# MT3608.net
KiCad netlist of a schematic drawn in Altium Designer
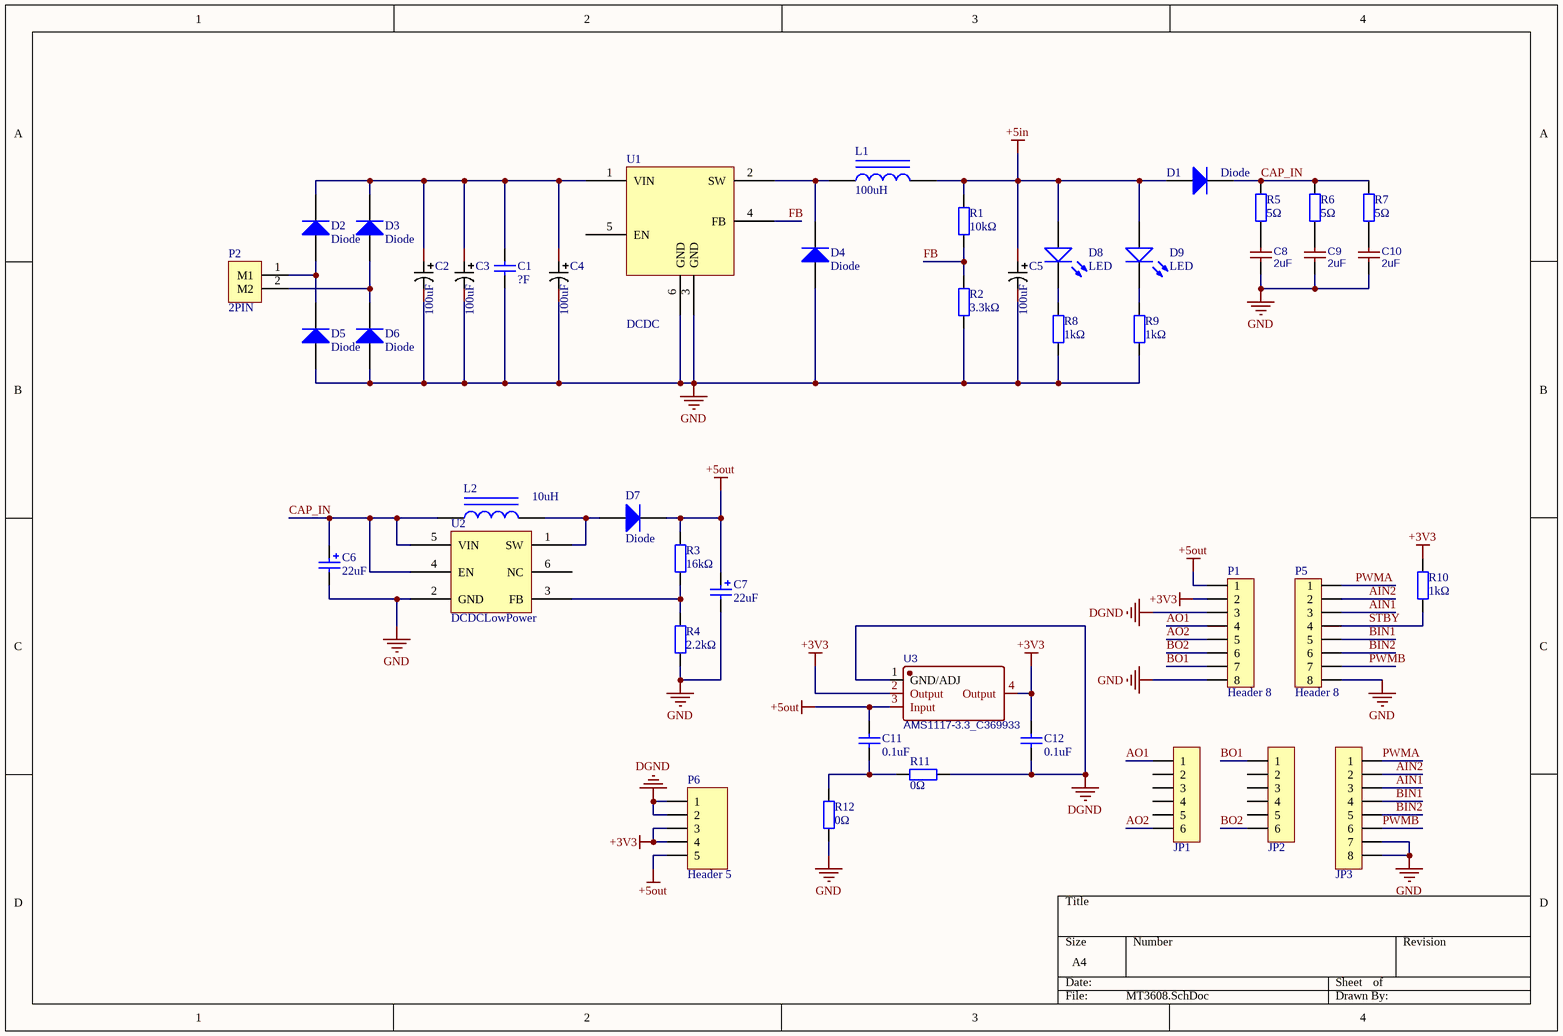
[diagram p0: MT3608.SchDoc]

(export (version "E")
  (design (tool "Eeschema 10.0.6"))
  (components
    (comp (ref "C1")
      (value "?F")
      (footprint "0603_C")
      (description "贴片电容")
      (libsource (lib "SFerret") (part "SMT_Cap"))
    )
    (comp (ref "C2")
      (value "100uF")
      (footprint "CM E(8*10.2)")
      (description "贴片电容")
      (libsource (lib "SFerret") (part "SMT_Cap_Electrolytic"))
    )
    (comp (ref "C3")
      (value "100uF")
      (footprint "CM E(8*10.2)")
      (description "贴片电容")
      (libsource (lib "SFerret") (part "SMT_Cap_Electrolytic"))
    )
    (comp (ref "C4")
      (value "100uF")
      (footprint "CM E(8*10.2)")
      (description "贴片电容")
      (libsource (lib "SFerret") (part "SMT_Cap_Electrolytic"))
    )
    (comp (ref "C5")
      (value "100uF")
      (footprint "CM E(8*10.2)")
      (description "贴片电容")
      (libsource (lib "SFerret") (part "SMT_Cap_Electrolytic"))
    )
    (comp (ref "C6")
      (value "22uF")
      (footprint "CASE-C_6032")
      (description "钽电容")
      (libsource (lib "SFerret") (part "SMT_Cap_Tantalum"))
    )
    (comp (ref "C7")
      (value "22uF")
      (footprint "CASE-C_6032")
      (description "钽电容")
      (libsource (lib "SFerret") (part "SMT_Cap_Tantalum"))
    )
    (comp (ref "C8")
      (value "2uF")
      (footprint "CAP-TH_L23.0-W10.0-P20.00-D1.4")
      (description "CBB，2uF电容")
      (fields
        (field (name "BOM_MANUFACTURER PART") "MPP205J4241119LC")
        (field (name "BOM_SUPPLIER PART") "C93266")
      )
      (libsource (lib "Schlib1") (part "2uF-CBB"))
    )
    (comp (ref "C9")
      (value "2uF")
      (footprint "CAP-TH_L23.0-W10.0-P20.00-D1.4")
      (description "CBB，2uF电容")
      (fields
        (field (name "BOM_MANUFACTURER PART") "MPP205J4241119LC")
        (field (name "BOM_SUPPLIER PART") "C93266")
      )
      (libsource (lib "Schlib1") (part "2uF-CBB"))
    )
    (comp (ref "C10")
      (value "2uF")
      (footprint "CAP-TH_L23.0-W10.0-P20.00-D1.4")
      (description "CBB，2uF电容")
      (fields
        (field (name "BOM_MANUFACTURER PART") "MPP205J4241119LC")
        (field (name "BOM_SUPPLIER PART") "C93266")
      )
      (libsource (lib "Schlib1") (part "2uF-CBB"))
    )
    (comp (ref "C11")
      (value "0.1uF")
      (footprint "0603_C")
      (description "贴片电容")
      (libsource (lib "SFerret") (part "SMT_Cap"))
    )
    (comp (ref "C12")
      (value "0.1uF")
      (footprint "0603_C")
      (description "贴片电容")
      (libsource (lib "SFerret") (part "SMT_Cap"))
    )
    (comp (ref "D1")
      (value "Diode")
      (footprint "SMA(DO-214AC)_S1")
      (description "通用二极管")
      (libsource (lib "SFerret") (part "Diode"))
    )
    (comp (ref "D2")
      (value "Diode")
      (footprint "SMA(DO-214AC)_S2")
      (description "通用二极管")
      (libsource (lib "SFerret") (part "Diode"))
    )
    (comp (ref "D3")
      (value "Diode")
      (footprint "SMA(DO-214AC)_S2")
      (description "通用二极管")
      (libsource (lib "SFerret") (part "Diode"))
    )
    (comp (ref "D4")
      (value "Diode")
      (footprint "SMA(DO-214AC)_S1")
      (description "通用二极管")
      (libsource (lib "SFerret") (part "Diode"))
    )
    (comp (ref "D5")
      (value "Diode")
      (footprint "SMA(DO-214AC)_S2")
      (description "通用二极管")
      (libsource (lib "SFerret") (part "Diode"))
    )
    (comp (ref "D6")
      (value "Diode")
      (footprint "SMA(DO-214AC)_S2")
      (description "通用二极管")
      (libsource (lib "SFerret") (part "Diode"))
    )
    (comp (ref "D7")
      (value "Diode")
      (footprint "SMA(DO-214AC)_S1")
      (description "通用二极管")
      (libsource (lib "SFerret") (part "Diode"))
    )
    (comp (ref "D8")
      (value "LED")
      (footprint "0805_LED")
      (description "发光二极管")
      (libsource (lib "SFerret") (part "LED"))
    )
    (comp (ref "D9")
      (value "LED")
      (footprint "0805_LED")
      (description "发光二极管")
      (libsource (lib "SFerret") (part "LED"))
    )
    (comp (ref "JP1")
      (value "HDR-1X6")
      (footprint "HDR2.54-WS-6P")
      (description "6P接插件")
      (libsource (lib "SFerret") (part "Header 6"))
    )
    (comp (ref "JP2")
      (value "HDR-1X6")
      (footprint "HDR2.54-WS-6P")
      (description "6P接插件")
      (libsource (lib "SFerret") (part "Header 6"))
    )
    (comp (ref "JP3")
      (value "HDR-1X8")
      (footprint "HDR2.54-WS-8P")
      (description "8P接插件")
      (libsource (lib "SFerret") (part "Header 8"))
    )
    (comp (ref "L1")
      (value "100uH")
      (footprint "CDRH127")
      (description "功率电感")
      (libsource (lib "SFerret") (part "SMT_Iud_Power"))
    )
    (comp (ref "L2")
      (value "10uH")
      (footprint "CDRH73")
      (description "功率电感")
      (libsource (lib "SFerret") (part "SMT_Iud_Power"))
    )
    (comp (ref "P1")
      (value "Header 8")
      (footprint "Header 8")
      (description "排针")
      (libsource (lib "") (part "Header 8_1"))
    )
    (comp (ref "P2") (value "2PIN") (footprint "KF128-2P") (libsource (lib "集大电协1.5") (part "接线端子-2PIN")))
    (comp (ref "P5")
      (value "Header 8")
      (footprint "Header 8")
      (description "排针")
      (libsource (lib "集大电协1.5") (part "Header 8"))
    )
    (comp (ref "P6")
      (value "Header 5")
      (footprint "HDR2.54-WS-5P")
      (description "排针")
      (libsource (lib "SFerret") (part "Header 5"))
    )
    (comp (ref "R1")
      (value "10kΩ")
      (footprint "0603_R")
      (description "贴片电阻")
      (libsource (lib "SFerret") (part "SMT_Res"))
    )
    (comp (ref "R2")
      (value "3.3kΩ")
      (footprint "0603_R")
      (description "贴片电阻")
      (libsource (lib "SFerret") (part "SMT_Res"))
    )
    (comp (ref "R3")
      (value "16kΩ")
      (footprint "0603_R")
      (description "贴片电阻")
      (libsource (lib "SFerret") (part "SMT_Res"))
    )
    (comp (ref "R4")
      (value "2.2kΩ")
      (footprint "0603_R")
      (description "贴片电阻")
      (libsource (lib "SFerret") (part "SMT_Res"))
    )
    (comp (ref "R5")
      (value "5Ω")
      (footprint "0603_R")
      (description "贴片电阻")
      (libsource (lib "SFerret") (part "SMT_Res"))
    )
    (comp (ref "R6")
      (value "5Ω")
      (footprint "0603_R")
      (description "贴片电阻")
      (libsource (lib "SFerret") (part "SMT_Res"))
    )
    (comp (ref "R7")
      (value "5Ω")
      (footprint "0603_R")
      (description "贴片电阻")
      (libsource (lib "SFerret") (part "SMT_Res"))
    )
    (comp (ref "R8")
      (value "1kΩ")
      (footprint "0603_R")
      (description "贴片电阻")
      (libsource (lib "SFerret") (part "SMT_Res"))
    )
    (comp (ref "R9")
      (value "1kΩ")
      (footprint "0603_R")
      (description "贴片电阻")
      (libsource (lib "SFerret") (part "SMT_Res"))
    )
    (comp (ref "R10")
      (value "1kΩ")
      (footprint "0603_R")
      (description "贴片电阻")
      (libsource (lib "SFerret") (part "SMT_Res"))
    )
    (comp (ref "R11")
      (value "0Ω")
      (footprint "1206_R")
      (description "贴片电阻")
      (libsource (lib "") (part "SMT_Res_1"))
    )
    (comp (ref "R12")
      (value "0Ω")
      (footprint "1206_R")
      (description "贴片电阻")
      (libsource (lib "SFerret") (part "SMT_Res"))
    )
    (comp (ref "U1")
      (value "DCDC")
      (footprint "TO-252-XL")
      (description "宽输入DCDC升降压管理芯片（Buck）")
      (libsource (lib "SFerret") (part "XL7015"))
    )
    (comp (ref "U2")
      (value "DCDCLowPower")
      (footprint "SOT95P290X145-6N")
      (libsource (lib "SFerret") (part "MT3608"))
    )
    (comp (ref "U3")
      (value "AMS1117-3.3_C369933")
      (footprint "SOT-223-4_L6.5-W3.5-P2.30-LS7.0-BR")
      (fields
        (field (name "BOM_SUPPLIER PART") "C369933")
        (field (name "BOM_MANUFACTURER PART") "AMS1117-3.3")
        (field (name "CONTRIBUTOR") "LCSC")
      )
      (libsource (lib "Schlib1") (part "AMS1117-3.3_C369933"))
    )
  )
  (nets
    (net (code "1") (name "+3V3") (class "Default")
      (node (ref "C12") (pin "2") (pinfunction "2_2") (pintype "passive"))
      (node (ref "P1") (pin "2") (pinfunction "2_2") (pintype "passive"))
      (node (ref "P6") (pin "3") (pinfunction "3_3") (pintype "passive"))
      (node (ref "P6") (pin "4") (pinfunction "4_4") (pintype "passive"))
      (node (ref "R10") (pin "2") (pinfunction "2_2") (pintype "passive"))
      (node (ref "U3") (pin "2") (pinfunction "Output_2") (pintype "passive"))
      (node (ref "U3") (pin "4") (pinfunction "Output_4") (pintype "passive"))
    )
    (net (code "2") (name "+5in") (class "Default")
      (node (ref "C5") (pin "1") (pinfunction "1_1") (pintype "passive"))
      (node (ref "D1") (pin "1") (pinfunction "A_1") (pintype "passive"))
      (node (ref "D8") (pin "A") (pinfunction "A_A") (pintype "passive"))
      (node (ref "D9") (pin "A") (pinfunction "A_A") (pintype "passive"))
      (node (ref "L1") (pin "2") (pinfunction "2_2") (pintype "passive"))
      (node (ref "R1") (pin "2") (pinfunction "2_2") (pintype "passive"))
    )
    (net (code "3") (name "+5out") (class "Default")
      (node (ref "C11") (pin "2") (pinfunction "2_2") (pintype "passive"))
      (node (ref "C7") (pin "1") (pinfunction "1_1") (pintype "passive"))
      (node (ref "D7") (pin "2") (pinfunction "K_2") (pintype "passive"))
      (node (ref "P1") (pin "1") (pinfunction "1_1") (pintype "passive"))
      (node (ref "P6") (pin "5") (pinfunction "5_5") (pintype "passive"))
      (node (ref "R3") (pin "2") (pinfunction "2_2") (pintype "passive"))
      (node (ref "U3") (pin "3") (pinfunction "Input_3") (pintype "passive"))
    )
    (net (code "4") (name "/AIN1") (class "Default")
      (node (ref "JP3") (pin "3") (pinfunction "3_3") (pintype "passive"))
      (node (ref "P5") (pin "3") (pinfunction "3_3") (pintype "passive"))
    )
    (net (code "5") (name "/AIN2") (class "Default")
      (node (ref "JP3") (pin "2") (pinfunction "2_2") (pintype "passive"))
      (node (ref "P5") (pin "2") (pinfunction "2_2") (pintype "passive"))
    )
    (net (code "6") (name "/AO1") (class "Default")
      (node (ref "JP1") (pin "1") (pinfunction "1_1") (pintype "passive"))
      (node (ref "P1") (pin "4") (pinfunction "4_4") (pintype "passive"))
    )
    (net (code "7") (name "/AO2") (class "Default")
      (node (ref "JP1") (pin "6") (pinfunction "6_6") (pintype "passive"))
      (node (ref "P1") (pin "5") (pinfunction "5_5") (pintype "passive"))
    )
    (net (code "8") (name "/BIN1") (class "Default")
      (node (ref "JP3") (pin "4") (pinfunction "4_4") (pintype "passive"))
      (node (ref "P5") (pin "5") (pinfunction "5_5") (pintype "passive"))
    )
    (net (code "9") (name "/BIN2") (class "Default")
      (node (ref "JP3") (pin "5") (pinfunction "5_5") (pintype "passive"))
      (node (ref "P5") (pin "6") (pinfunction "6_6") (pintype "passive"))
    )
    (net (code "10") (name "/BO1") (class "Default")
      (node (ref "JP2") (pin "1") (pinfunction "1_1") (pintype "passive"))
      (node (ref "P1") (pin "7") (pinfunction "7_7") (pintype "passive"))
    )
    (net (code "11") (name "/BO2") (class "Default")
      (node (ref "JP2") (pin "6") (pinfunction "6_6") (pintype "passive"))
      (node (ref "P1") (pin "6") (pinfunction "6_6") (pintype "passive"))
    )
    (net (code "12") (name "/CAP_IN") (class "Default")
      (node (ref "C6") (pin "1") (pinfunction "1_1") (pintype "passive"))
      (node (ref "D1") (pin "2") (pinfunction "K_2") (pintype "passive"))
      (node (ref "L2") (pin "1") (pinfunction "1_1") (pintype "passive"))
      (node (ref "R5") (pin "2") (pinfunction "2_2") (pintype "passive"))
      (node (ref "R6") (pin "2") (pinfunction "2_2") (pintype "passive"))
      (node (ref "R7") (pin "2") (pinfunction "2_2") (pintype "passive"))
      (node (ref "U2") (pin "4") (pinfunction "EN_4") (pintype "passive"))
      (node (ref "U2") (pin "5") (pinfunction "VIN_5") (pintype "passive"))
    )
    (net (code "13") (name "/FB") (class "Default")
      (node (ref "R1") (pin "1") (pinfunction "1_1") (pintype "passive"))
      (node (ref "R2") (pin "2") (pinfunction "2_2") (pintype "passive"))
      (node (ref "U1") (pin "4") (pinfunction "FB_4") (pintype "passive"))
    )
    (net (code "14") (name "/PWMA") (class "Default")
      (node (ref "JP3") (pin "1") (pinfunction "1_1") (pintype "passive"))
      (node (ref "P5") (pin "1") (pinfunction "1_1") (pintype "passive"))
    )
    (net (code "15") (name "/PWMB") (class "Default")
      (node (ref "JP3") (pin "6") (pinfunction "6_6") (pintype "passive"))
      (node (ref "P5") (pin "7") (pinfunction "7_7") (pintype "passive"))
    )
    (net (code "16") (name "/STBY") (class "Default")
      (node (ref "P5") (pin "4") (pinfunction "4_4") (pintype "passive"))
      (node (ref "R10") (pin "1") (pinfunction "1_1") (pintype "passive"))
    )
    (net (code "17") (name "DGND") (class "Default")
      (node (ref "C12") (pin "1") (pinfunction "1_1") (pintype "passive"))
      (node (ref "P1") (pin "3") (pinfunction "3_3") (pintype "passive"))
      (node (ref "P6") (pin "1") (pinfunction "1_1") (pintype "passive"))
      (node (ref "P6") (pin "2") (pinfunction "2_2") (pintype "passive"))
      (node (ref "R11") (pin "1") (pinfunction "1_1") (pintype "passive"))
      (node (ref "U3") (pin "1") (pinfunction "GND/ADJ_1") (pintype "passive"))
    )
    (net (code "18") (name "GND") (class "Default")
      (node (ref "C1") (pin "1") (pinfunction "1_1") (pintype "passive"))
      (node (ref "C10") (pin "1") (pinfunction "1_1") (pintype "passive"))
      (node (ref "C2") (pin "2") (pinfunction "2_2") (pintype "passive"))
      (node (ref "C3") (pin "2") (pinfunction "2_2") (pintype "passive"))
      (node (ref "C4") (pin "2") (pinfunction "2_2") (pintype "passive"))
      (node (ref "C5") (pin "2") (pinfunction "2_2") (pintype "passive"))
      (node (ref "C6") (pin "2") (pinfunction "2_2") (pintype "passive"))
      (node (ref "C7") (pin "2") (pinfunction "2_2") (pintype "passive"))
      (node (ref "C8") (pin "1") (pinfunction "1_1") (pintype "passive"))
      (node (ref "C9") (pin "1") (pinfunction "1_1") (pintype "passive"))
      (node (ref "D4") (pin "1") (pinfunction "A_1") (pintype "passive"))
      (node (ref "D5") (pin "1") (pinfunction "A_1") (pintype "passive"))
      (node (ref "D6") (pin "1") (pinfunction "A_1") (pintype "passive"))
      (node (ref "JP3") (pin "7") (pinfunction "7_7") (pintype "passive"))
      (node (ref "JP3") (pin "8") (pinfunction "8_8") (pintype "passive"))
      (node (ref "P1") (pin "8") (pinfunction "8_8") (pintype "passive"))
      (node (ref "P5") (pin "8") (pinfunction "8_8") (pintype "passive"))
      (node (ref "R12") (pin "1") (pinfunction "1_1") (pintype "passive"))
      (node (ref "R2") (pin "1") (pinfunction "1_1") (pintype "passive"))
      (node (ref "R4") (pin "1") (pinfunction "1_1") (pintype "passive"))
      (node (ref "R8") (pin "1") (pinfunction "1_1") (pintype "passive"))
      (node (ref "R9") (pin "1") (pinfunction "1_1") (pintype "passive"))
      (node (ref "U1") (pin "3") (pinfunction "GND_3") (pintype "passive"))
      (node (ref "U1") (pin "6") (pinfunction "GND_6") (pintype "passive"))
      (node (ref "U2") (pin "2") (pinfunction "GND_2") (pintype "passive"))
    )
    (net (code "19") (name "Net-(C8-Pad2)") (class "Default")
      (node (ref "C8") (pin "2") (pinfunction "2_2") (pintype "passive"))
      (node (ref "R5") (pin "1") (pinfunction "1_1") (pintype "passive"))
    )
    (net (code "20") (name "Net-(C9-Pad2)") (class "Default")
      (node (ref "C9") (pin "2") (pinfunction "2_2") (pintype "passive"))
      (node (ref "R6") (pin "1") (pinfunction "1_1") (pintype "passive"))
    )
    (net (code "21") (name "Net-(C10-Pad2)") (class "Default")
      (node (ref "C10") (pin "2") (pinfunction "2_2") (pintype "passive"))
      (node (ref "R7") (pin "1") (pinfunction "1_1") (pintype "passive"))
    )
    (net (code "22") (name "Net-(C11-Pad1)") (class "Default")
      (node (ref "C11") (pin "1") (pinfunction "1_1") (pintype "passive"))
      (node (ref "R11") (pin "2") (pinfunction "2_2") (pintype "passive"))
      (node (ref "R12") (pin "2") (pinfunction "2_2") (pintype "passive"))
    )
    (net (code "23") (name "Net-(D2-A)") (class "Default")
      (node (ref "D2") (pin "1") (pinfunction "A_1") (pintype "passive"))
      (node (ref "D5") (pin "2") (pinfunction "K_2") (pintype "passive"))
      (node (ref "P2") (pin "1") (pinfunction "M1_1") (pintype "passive"))
    )
    (net (code "24") (name "Net-(D2-K)") (class "Default")
      (node (ref "C1") (pin "2") (pinfunction "2_2") (pintype "passive"))
      (node (ref "C2") (pin "1") (pinfunction "1_1") (pintype "passive"))
      (node (ref "C3") (pin "1") (pinfunction "1_1") (pintype "passive"))
      (node (ref "C4") (pin "1") (pinfunction "1_1") (pintype "passive"))
      (node (ref "D2") (pin "2") (pinfunction "K_2") (pintype "passive"))
      (node (ref "D3") (pin "2") (pinfunction "K_2") (pintype "passive"))
      (node (ref "U1") (pin "1") (pinfunction "VIN_1") (pintype "passive"))
    )
    (net (code "25") (name "Net-(D3-A)") (class "Default")
      (node (ref "D3") (pin "1") (pinfunction "A_1") (pintype "passive"))
      (node (ref "D6") (pin "2") (pinfunction "K_2") (pintype "passive"))
      (node (ref "P2") (pin "2") (pinfunction "M2_2") (pintype "passive"))
    )
    (net (code "26") (name "Net-(D4-K)") (class "Default")
      (node (ref "D4") (pin "2") (pinfunction "K_2") (pintype "passive"))
      (node (ref "L1") (pin "1") (pinfunction "1_1") (pintype "passive"))
      (node (ref "U1") (pin "2") (pinfunction "SW_2") (pintype "passive"))
    )
    (net (code "27") (name "Net-(D7-A)") (class "Default")
      (node (ref "D7") (pin "1") (pinfunction "A_1") (pintype "passive"))
      (node (ref "L2") (pin "2") (pinfunction "2_2") (pintype "passive"))
      (node (ref "U2") (pin "1") (pinfunction "SW_1") (pintype "passive"))
    )
    (net (code "28") (name "Net-(D8-PadK)") (class "Default")
      (node (ref "D8") (pin "K") (pinfunction "K_K") (pintype "passive"))
      (node (ref "R8") (pin "2") (pinfunction "2_2") (pintype "passive"))
    )
    (net (code "29") (name "Net-(D9-PadK)") (class "Default")
      (node (ref "D9") (pin "K") (pinfunction "K_K") (pintype "passive"))
      (node (ref "R9") (pin "2") (pinfunction "2_2") (pintype "passive"))
    )
    (net (code "30") (name "Net-(U2-FB)") (class "Default")
      (node (ref "R3") (pin "1") (pinfunction "1_1") (pintype "passive"))
      (node (ref "R4") (pin "2") (pinfunction "2_2") (pintype "passive"))
      (node (ref "U2") (pin "3") (pinfunction "FB_3") (pintype "passive"))
    )
    (net (code "31") (name "unconnected-(JP1-Pad2)") (class "Default")
      (node (ref "JP1") (pin "2") (pinfunction "2_2") (pintype "passive"))
    )
    (net (code "32") (name "unconnected-(JP1-Pad3)") (class "Default")
      (node (ref "JP1") (pin "3") (pinfunction "3_3") (pintype "passive"))
    )
    (net (code "33") (name "unconnected-(JP1-Pad4)") (class "Default")
      (node (ref "JP1") (pin "4") (pinfunction "4_4") (pintype "passive"))
    )
    (net (code "34") (name "unconnected-(JP1-Pad5)") (class "Default")
      (node (ref "JP1") (pin "5") (pinfunction "5_5") (pintype "passive"))
    )
    (net (code "35") (name "unconnected-(JP2-Pad2)") (class "Default")
      (node (ref "JP2") (pin "2") (pinfunction "2_2") (pintype "passive"))
    )
    (net (code "36") (name "unconnected-(JP2-Pad3)") (class "Default")
      (node (ref "JP2") (pin "3") (pinfunction "3_3") (pintype "passive"))
    )
    (net (code "37") (name "unconnected-(JP2-Pad4)") (class "Default")
      (node (ref "JP2") (pin "4") (pinfunction "4_4") (pintype "passive"))
    )
    (net (code "38") (name "unconnected-(JP2-Pad5)") (class "Default")
      (node (ref "JP2") (pin "5") (pinfunction "5_5") (pintype "passive"))
    )
    (net (code "39") (name "unconnected-(U1-EN-Pad5)") (class "Default")
      (node (ref "U1") (pin "5") (pinfunction "EN_5") (pintype "passive"))
    )
    (net (code "40") (name "unconnected-(U2-NC-Pad6)") (class "Default")
      (node (ref "U2") (pin "6") (pinfunction "NC_6") (pintype "passive"))
    )
  )
)
